# Wonderswan_1_5v_regulator_EasyEDA.net
KiCad netlist of a schematic drawn in EasyEDA
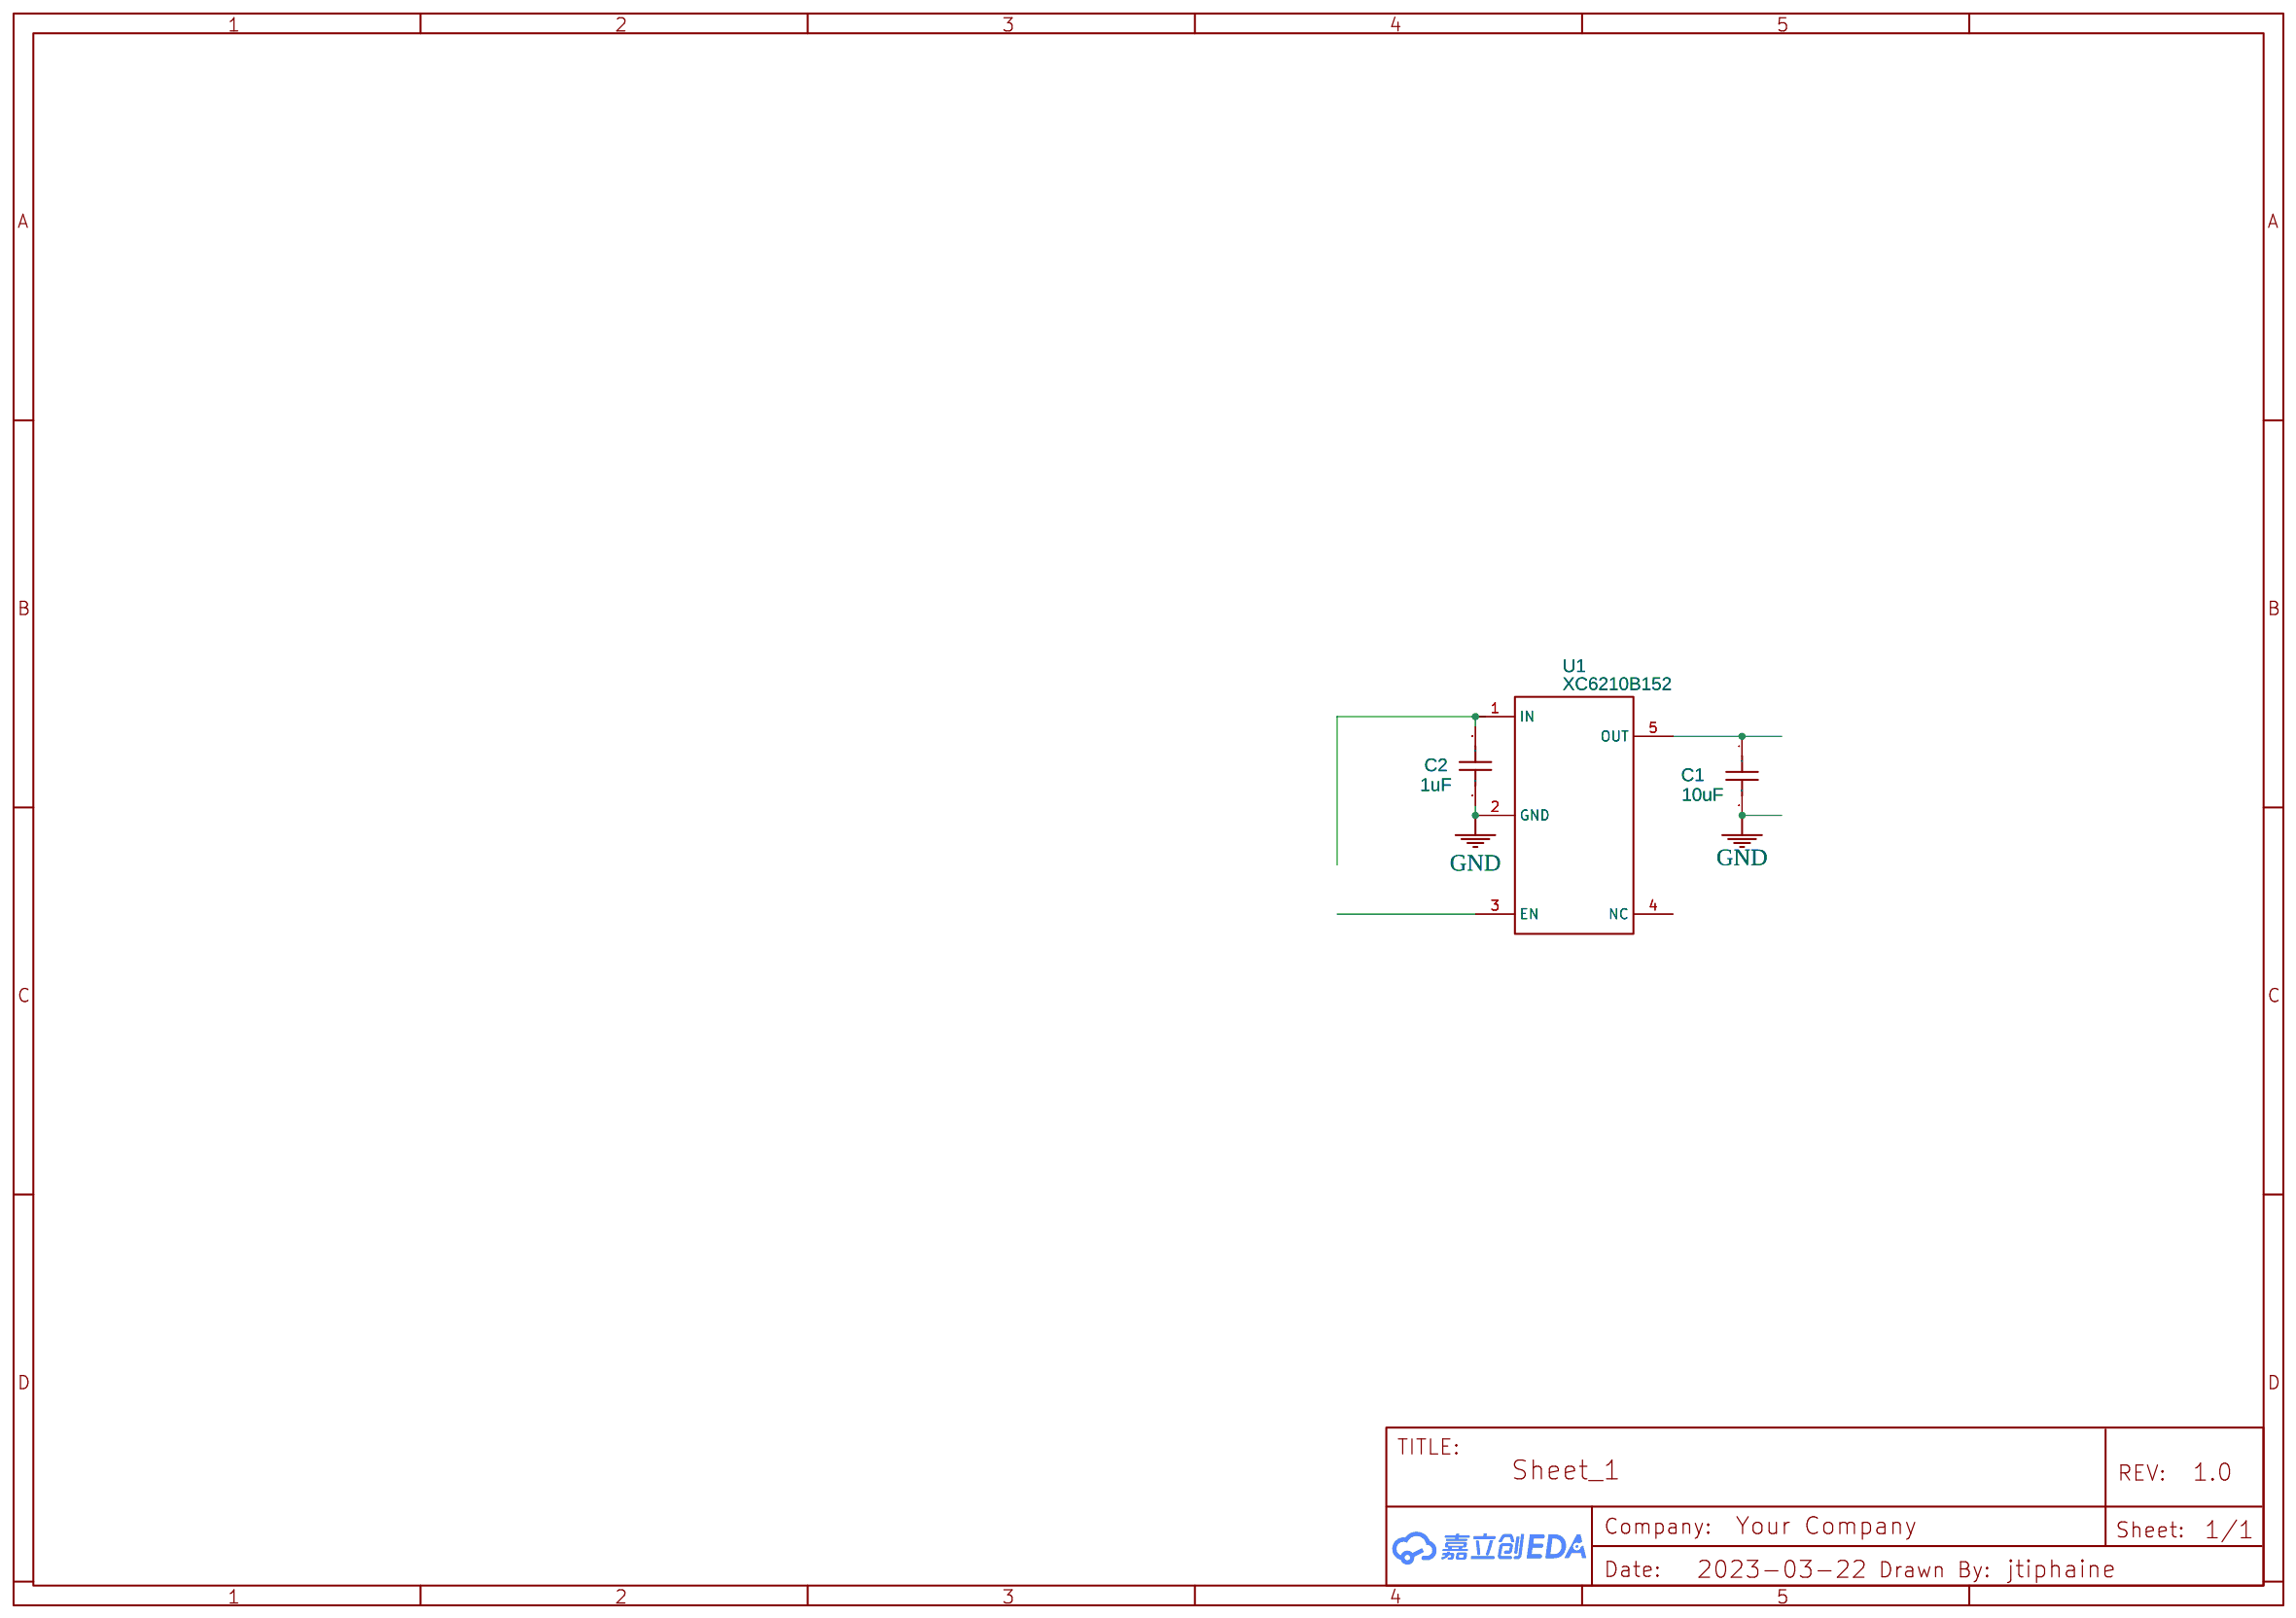
[diagram p0: schematic sheet]

(export (version "E")
  (design (tool "Eeschema 10.0.6"))
  (components
    (comp (ref "C1")
      (value "10uF")
      (fields
        (field (name "BOM_Manufacturer Part") "0805X106K160NT")
        (field (name "BOM_Supplier Part") "C89189")
      )
      (libsource (lib "") (part "0805X106K160NT"))
    )
    (comp (ref "C2")
      (value "1uF")
      (fields
        (field (name "BOM_Manufacturer Part") "0805B105K250NT")
        (field (name "BOM_Supplier Part") "C89190")
      )
      (libsource (lib "") (part "0805B105K250NT"))
    )
    (comp (ref "U1")
      (value "XC6210B152")
      (fields
        (field (name "BOM_Manufacturer Part") "XC6210B152MR-G")
        (field (name "BOM_Supplier Part") "865-XC6210B152MR-G")
      )
      (libsource (lib "") (part "XC6210B152"))
    )
  )
  (nets
    (net (code "1") (name "GND") (class "Default")
      (node (ref "C1") (pin "2") (pinfunction "2_2") (pintype "unspecified"))
      (node (ref "C2") (pin "1") (pinfunction "1_1") (pintype "unspecified"))
      (node (ref "U1") (pin "2") (pinfunction "GND_2") (pintype "unspecified"))
    )
    (net (code "2") (name "Net-(U1-IN)") (class "Default")
      (node (ref "C2") (pin "2") (pinfunction "2_2") (pintype "unspecified"))
      (node (ref "U1") (pin "1") (pinfunction "IN_1") (pintype "unspecified"))
    )
    (net (code "3") (name "Net-(U1-OUT)") (class "Default")
      (node (ref "C1") (pin "1") (pinfunction "1_1") (pintype "unspecified"))
      (node (ref "U1") (pin "5") (pinfunction "OUT_5") (pintype "unspecified"))
    )
    (net (code "4") (name "unconnected-(U1-EN-Pad3)") (class "Default")
      (node (ref "U1") (pin "3") (pinfunction "EN_3") (pintype "unspecified"))
    )
    (net (code "5") (name "unconnected-(U1-NC-Pad4)") (class "Default")
      (node (ref "U1") (pin "4") (pinfunction "NC_4") (pintype "unspecified"))
    )
  )
)
